# PulseSensorRing.net
KiCad netlist of a schematic drawn in EAGLE
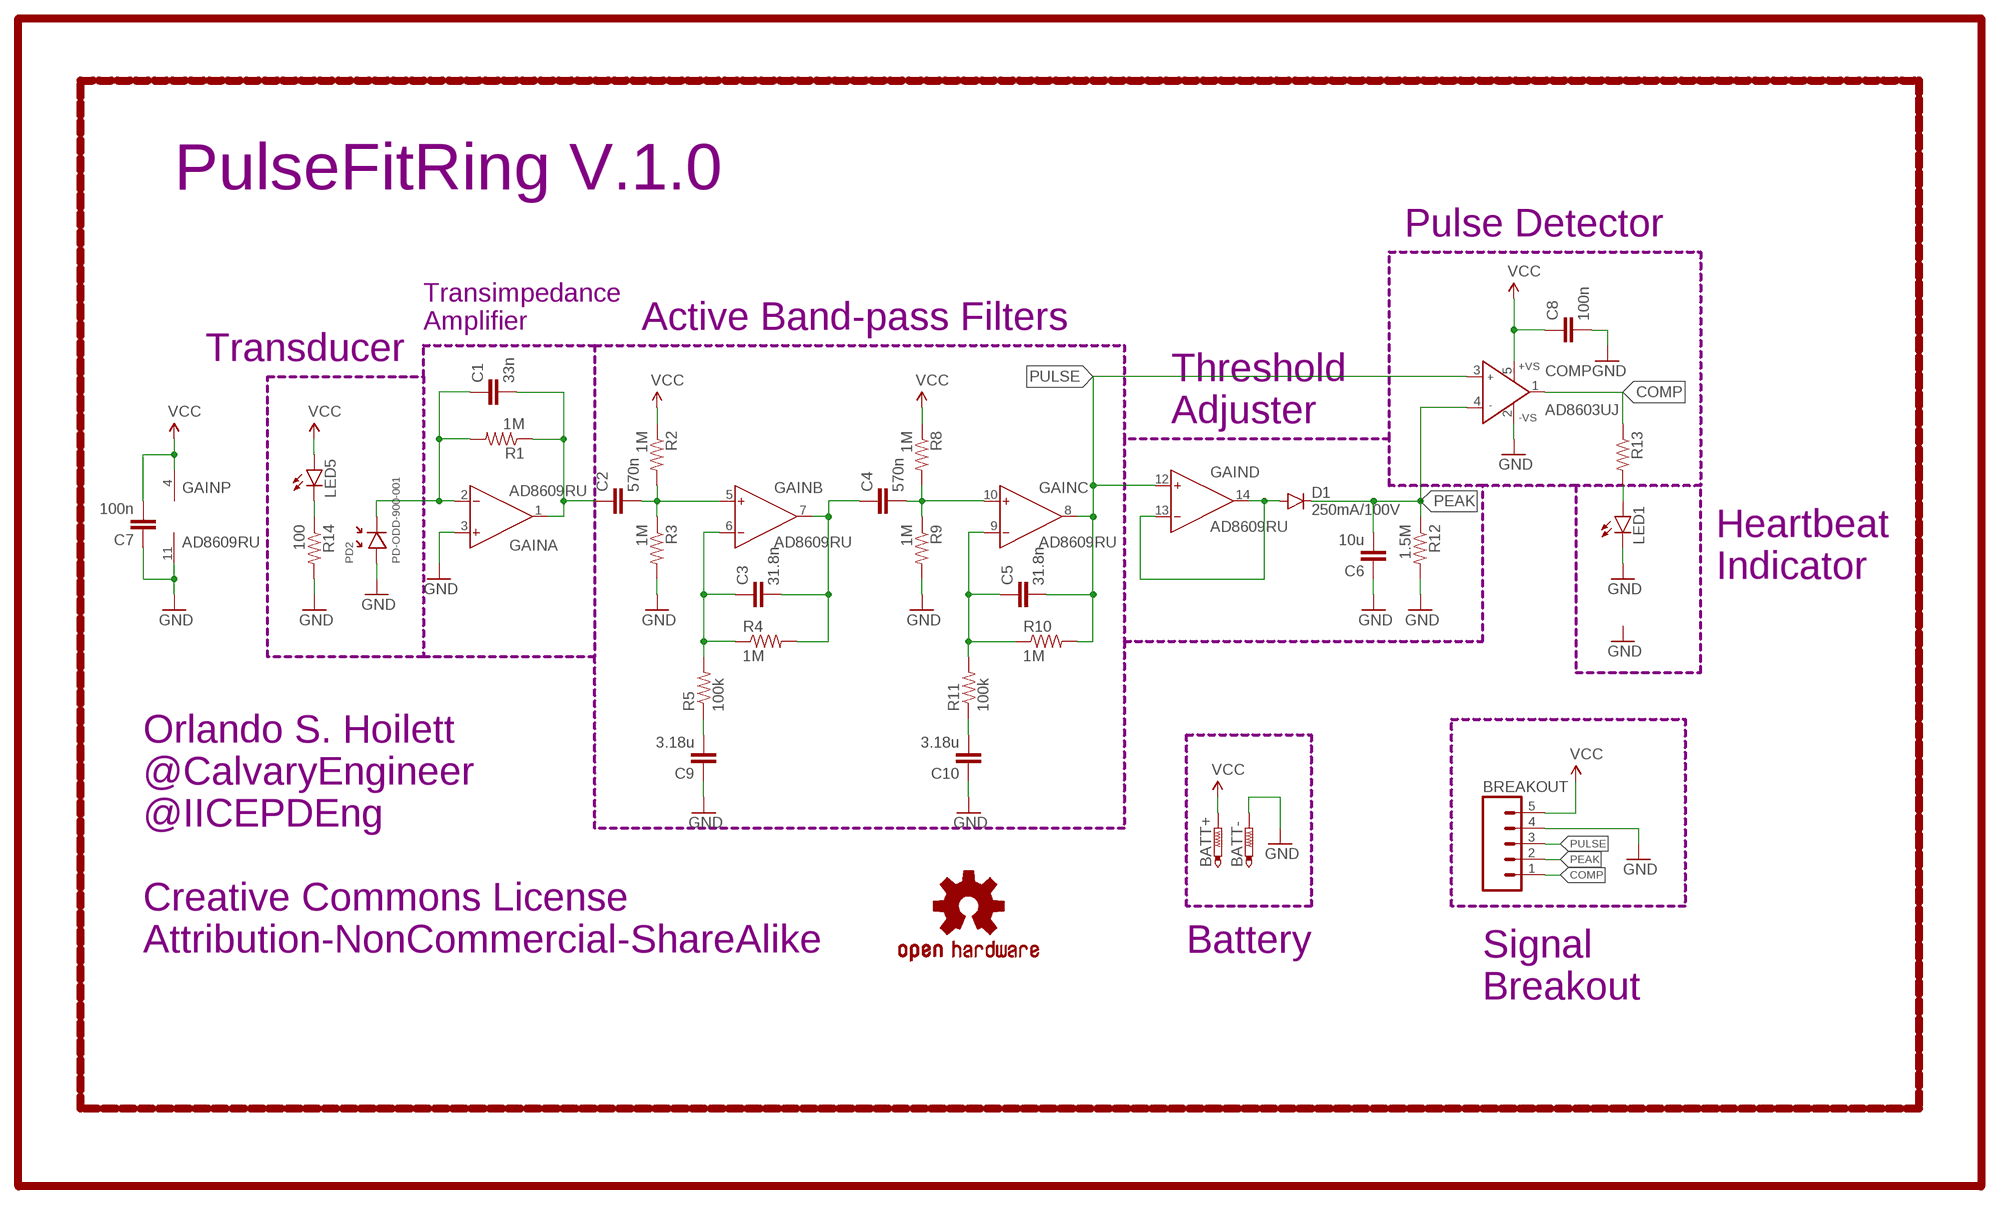
[diagram p0: schematic, sheet 1]

(export (version "E")
  (design (tool "Eeschema 10.0.6"))
  (components
    (comp (ref "BATT")
      (value "BATT-CONNECT")
      (footprint "eagle-import:HOLE")
      (libsource (lib "eagle-import") (part "BATT-CONNECT"))
    )
    (comp (ref "BREAKOUT")
      (value "M05NO_SILK")
      (footprint "eagle-import:1X05_NO_SILK")
      (libsource (lib "eagle-import") (part "M05NO_SILK"))
    )
    (comp (ref "C1")
      (value "33n")
      (footprint "eagle-import:C0402")
      (libsource (lib "eagle-import") (part "C-EUC0402"))
    )
    (comp (ref "C2")
      (value "570n")
      (footprint "eagle-import:C0402")
      (libsource (lib "eagle-import") (part "C-EUC0402"))
    )
    (comp (ref "C3")
      (value "31.8n")
      (footprint "eagle-import:C0402")
      (libsource (lib "eagle-import") (part "C-EUC0402"))
    )
    (comp (ref "C4")
      (value "570n")
      (footprint "eagle-import:C0402")
      (libsource (lib "eagle-import") (part "C-EUC0402"))
    )
    (comp (ref "C5")
      (value "31.8n")
      (footprint "eagle-import:C0402")
      (libsource (lib "eagle-import") (part "C-EUC0402"))
    )
    (comp (ref "C6")
      (value "10u")
      (footprint "eagle-import:C0402")
      (libsource (lib "eagle-import") (part "C-EUC0402"))
    )
    (comp (ref "C7")
      (value "100n")
      (footprint "eagle-import:C0402")
      (libsource (lib "eagle-import") (part "C-EUC0402"))
    )
    (comp (ref "C8")
      (value "100n")
      (footprint "eagle-import:C0402")
      (libsource (lib "eagle-import") (part "C-EUC0402"))
    )
    (comp (ref "C9")
      (value "3.18u")
      (footprint "eagle-import:C0402")
      (libsource (lib "eagle-import") (part "C-EUC0402"))
    )
    (comp (ref "C10")
      (value "3.18u")
      (footprint "eagle-import:C0402")
      (libsource (lib "eagle-import") (part "C-EUC0402"))
    )
    (comp (ref "COMP")
      (value "AD8603UJ")
      (footprint "eagle-import:SOT23-5")
      (fields (field (name "MF") "ALTERA CORPORATION") (field (name "MPN") "AD8603AUJZ-REEL7"))
      (libsource (lib "eagle-import") (part "AD8603UJ"))
    )
    (comp (ref "D1")
      (value "250mA/100V")
      (footprint "eagle-import:SOD-323")
      (libsource (lib "eagle-import") (part "DIODEBAS16"))
    )
    (comp (ref "GAIN")
      (value "AD8609RU")
      (footprint "eagle-import:TSSOP14")
      (fields (field (name "MF") "ALTERA CORPORATION") (field (name "MPN") "AD8609ARUZ"))
      (libsource (lib "eagle-import") (part "AD8609RU"))
    )
    (comp (ref "LED1")
      (value "LED0603")
      (footprint "eagle-import:LED-0603")
      (libsource (lib "eagle-import") (part "LED0603"))
    )
    (comp (ref "LED5")
      (value "LED0603")
      (footprint "eagle-import:LED-0603")
      (libsource (lib "eagle-import") (part "LED0603"))
    )
    (comp (ref "LOGO1")
      (value "OSHW-LOGOS")
      (footprint "eagle-import:OSHW-LOGO-S")
      (libsource (lib "eagle-import") (part "OSHW-LOGOS"))
    )
    (comp (ref "PD2")
      (value "PD-ODD-900-001")
      (footprint "eagle-import:SMD-PD-01")
      (libsource (lib "eagle-import") (part "PD-ODD-900-001"))
    )
    (comp (ref "R1")
      (value "1M")
      (footprint "eagle-import:R0402")
      (libsource (lib "eagle-import") (part "R-US_R0402"))
    )
    (comp (ref "R2")
      (value "1M")
      (footprint "eagle-import:R0402")
      (libsource (lib "eagle-import") (part "R-US_R0402"))
    )
    (comp (ref "R3")
      (value "1M")
      (footprint "eagle-import:R0402")
      (libsource (lib "eagle-import") (part "R-US_R0402"))
    )
    (comp (ref "R4")
      (value "1M")
      (footprint "eagle-import:R0402")
      (libsource (lib "eagle-import") (part "R-US_R0402"))
    )
    (comp (ref "R5")
      (value "100k")
      (footprint "eagle-import:R0402")
      (libsource (lib "eagle-import") (part "R-US_R0402"))
    )
    (comp (ref "R8")
      (value "1M")
      (footprint "eagle-import:R0402")
      (libsource (lib "eagle-import") (part "R-US_R0402"))
    )
    (comp (ref "R9")
      (value "1M")
      (footprint "eagle-import:R0402")
      (libsource (lib "eagle-import") (part "R-US_R0402"))
    )
    (comp (ref "R10")
      (value "1M")
      (footprint "eagle-import:R0402")
      (libsource (lib "eagle-import") (part "R-US_R0402"))
    )
    (comp (ref "R11")
      (value "100k")
      (footprint "eagle-import:R0402")
      (libsource (lib "eagle-import") (part "R-US_R0402"))
    )
    (comp (ref "R12")
      (value "1.5M")
      (footprint "eagle-import:R0402")
      (libsource (lib "eagle-import") (part "R-US_R0402"))
    )
    (comp (ref "R13")
      (value "R-US_R0402")
      (footprint "eagle-import:R0402")
      (libsource (lib "eagle-import") (part "R-US_R0402"))
    )
    (comp (ref "R14")
      (value "100")
      (footprint "eagle-import:R0402")
      (libsource (lib "eagle-import") (part "R-US_R0402"))
    )
  )
  (nets
    (net (code "1") (name "COMP") (class "Default")
      (node (ref "BREAKOUT") (pin "1") (pinfunction "1_1") (pintype "passive"))
      (node (ref "COMP") (pin "1") (pinfunction "OUT_1") (pintype "output"))
      (node (ref "R13") (pin "1") (pinfunction "1_1") (pintype "passive"))
    )
    (net (code "2") (name "GND") (class "Default")
      (node (ref "BATT") (pin "P$2") (pinfunction "TP_P$2") (pintype "input"))
      (node (ref "BREAKOUT") (pin "4") (pinfunction "4_4") (pintype "passive"))
      (node (ref "C10") (pin "1") (pinfunction "1_1") (pintype "passive"))
      (node (ref "C6") (pin "1") (pinfunction "1_1") (pintype "passive"))
      (node (ref "C7") (pin "1") (pinfunction "1_1") (pintype "passive"))
      (node (ref "C8") (pin "2") (pinfunction "2_2") (pintype "passive"))
      (node (ref "C9") (pin "1") (pinfunction "1_1") (pintype "passive"))
      (node (ref "COMP") (pin "2") (pinfunction "-VS_2") (pintype "input"))
      (node (ref "GAIN") (pin "11") (pinfunction "V-_11") (pintype "power_in"))
      (node (ref "GAIN") (pin "3") (pinfunction "IN+_3") (pintype "input"))
      (node (ref "LED1") (pin "C") (pinfunction "C_C") (pintype "passive"))
      (node (ref "PD2") (pin "ANODE") (pinfunction "+_ANODE") (pintype "bidirectional"))
      (node (ref "R12") (pin "2") (pinfunction "2_2") (pintype "passive"))
      (node (ref "R14") (pin "2") (pinfunction "2_2") (pintype "passive"))
      (node (ref "R3") (pin "2") (pinfunction "2_2") (pintype "passive"))
      (node (ref "R9") (pin "2") (pinfunction "2_2") (pintype "passive"))
    )
    (net (code "3") (name "Net-(C9-Pad2)") (class "Default")
      (node (ref "C9") (pin "2") (pinfunction "2_2") (pintype "passive"))
      (node (ref "R5") (pin "1") (pinfunction "1_1") (pintype "passive"))
    )
    (net (code "4") (name "Net-(C10-Pad2)") (class "Default")
      (node (ref "C10") (pin "2") (pinfunction "2_2") (pintype "passive"))
      (node (ref "R11") (pin "1") (pinfunction "1_1") (pintype "passive"))
    )
    (net (code "5") (name "Net-(GAINA-IN-)") (class "Default")
      (node (ref "C1") (pin "1") (pinfunction "1_1") (pintype "passive"))
      (node (ref "GAIN") (pin "2") (pinfunction "IN-_2") (pintype "input"))
      (node (ref "PD2") (pin "CATHODE") (pinfunction "-_CATHODE") (pintype "bidirectional"))
      (node (ref "R1") (pin "2") (pinfunction "2_2") (pintype "passive"))
    )
    (net (code "6") (name "Net-(GAINA-OUT)") (class "Default")
      (node (ref "C1") (pin "2") (pinfunction "2_2") (pintype "passive"))
      (node (ref "C2") (pin "1") (pinfunction "1_1") (pintype "passive"))
      (node (ref "GAIN") (pin "1") (pinfunction "OUT_1") (pintype "output"))
      (node (ref "R1") (pin "1") (pinfunction "1_1") (pintype "passive"))
    )
    (net (code "7") (name "Net-(GAINB-IN+)") (class "Default")
      (node (ref "C2") (pin "2") (pinfunction "2_2") (pintype "passive"))
      (node (ref "GAIN") (pin "5") (pinfunction "IN+_5") (pintype "input"))
      (node (ref "R2") (pin "2") (pinfunction "2_2") (pintype "passive"))
      (node (ref "R3") (pin "1") (pinfunction "1_1") (pintype "passive"))
    )
    (net (code "8") (name "Net-(GAINB-IN-)") (class "Default")
      (node (ref "C3") (pin "1") (pinfunction "1_1") (pintype "passive"))
      (node (ref "GAIN") (pin "6") (pinfunction "IN-_6") (pintype "input"))
      (node (ref "R4") (pin "1") (pinfunction "1_1") (pintype "passive"))
      (node (ref "R5") (pin "2") (pinfunction "2_2") (pintype "passive"))
    )
    (net (code "9") (name "Net-(GAINB-OUT)") (class "Default")
      (node (ref "C3") (pin "2") (pinfunction "2_2") (pintype "passive"))
      (node (ref "C4") (pin "1") (pinfunction "1_1") (pintype "passive"))
      (node (ref "GAIN") (pin "7") (pinfunction "OUT_7") (pintype "output"))
      (node (ref "R4") (pin "2") (pinfunction "2_2") (pintype "passive"))
    )
    (net (code "10") (name "Net-(GAINC-IN+)") (class "Default")
      (node (ref "C4") (pin "2") (pinfunction "2_2") (pintype "passive"))
      (node (ref "GAIN") (pin "10") (pinfunction "IN+_10") (pintype "input"))
      (node (ref "R8") (pin "2") (pinfunction "2_2") (pintype "passive"))
      (node (ref "R9") (pin "1") (pinfunction "1_1") (pintype "passive"))
    )
    (net (code "11") (name "Net-(GAINC-IN-)") (class "Default")
      (node (ref "C5") (pin "1") (pinfunction "1_1") (pintype "passive"))
      (node (ref "GAIN") (pin "9") (pinfunction "IN-_9") (pintype "input"))
      (node (ref "R10") (pin "1") (pinfunction "1_1") (pintype "passive"))
      (node (ref "R11") (pin "2") (pinfunction "2_2") (pintype "passive"))
    )
    (net (code "12") (name "Net-(GAIND-IN-)") (class "Default")
      (node (ref "D1") (pin "A") (pinfunction "A_A") (pintype "passive"))
      (node (ref "GAIN") (pin "13") (pinfunction "IN-_13") (pintype "input"))
      (node (ref "GAIN") (pin "14") (pinfunction "OUT_14") (pintype "output"))
    )
    (net (code "13") (name "Net-(LED1-PadA)") (class "Default")
      (node (ref "LED1") (pin "A") (pinfunction "A_A") (pintype "passive"))
      (node (ref "R13") (pin "2") (pinfunction "2_2") (pintype "passive"))
    )
    (net (code "14") (name "Net-(LED5-PadC)") (class "Default")
      (node (ref "LED5") (pin "C") (pinfunction "C_C") (pintype "passive"))
      (node (ref "R14") (pin "1") (pinfunction "1_1") (pintype "passive"))
    )
    (net (code "15") (name "PEAK") (class "Default")
      (node (ref "BREAKOUT") (pin "2") (pinfunction "2_2") (pintype "passive"))
      (node (ref "C6") (pin "2") (pinfunction "2_2") (pintype "passive"))
      (node (ref "COMP") (pin "4") (pinfunction "IN-_4") (pintype "input"))
      (node (ref "D1") (pin "C") (pinfunction "C_C") (pintype "passive"))
      (node (ref "R12") (pin "1") (pinfunction "1_1") (pintype "passive"))
    )
    (net (code "16") (name "PULSE") (class "Default")
      (node (ref "BREAKOUT") (pin "3") (pinfunction "3_3") (pintype "passive"))
      (node (ref "C5") (pin "2") (pinfunction "2_2") (pintype "passive"))
      (node (ref "COMP") (pin "3") (pinfunction "IN+_3") (pintype "input"))
      (node (ref "GAIN") (pin "12") (pinfunction "IN+_12") (pintype "input"))
      (node (ref "GAIN") (pin "8") (pinfunction "OUT_8") (pintype "output"))
      (node (ref "R10") (pin "2") (pinfunction "2_2") (pintype "passive"))
    )
    (net (code "17") (name "VCC") (class "Default")
      (node (ref "BATT") (pin "P$1") (pinfunction "TP_P$1") (pintype "input"))
      (node (ref "BREAKOUT") (pin "5") (pinfunction "5_5") (pintype "passive"))
      (node (ref "C7") (pin "2") (pinfunction "2_2") (pintype "passive"))
      (node (ref "C8") (pin "1") (pinfunction "1_1") (pintype "passive"))
      (node (ref "COMP") (pin "5") (pinfunction "+VS_5") (pintype "input"))
      (node (ref "GAIN") (pin "4") (pinfunction "V+_4") (pintype "power_in"))
      (node (ref "LED5") (pin "A") (pinfunction "A_A") (pintype "passive"))
      (node (ref "R2") (pin "1") (pinfunction "1_1") (pintype "passive"))
      (node (ref "R8") (pin "1") (pinfunction "1_1") (pintype "passive"))
    )
  )
)
